# equ.net
KiCad netlist of a schematic drawn in EAGLE
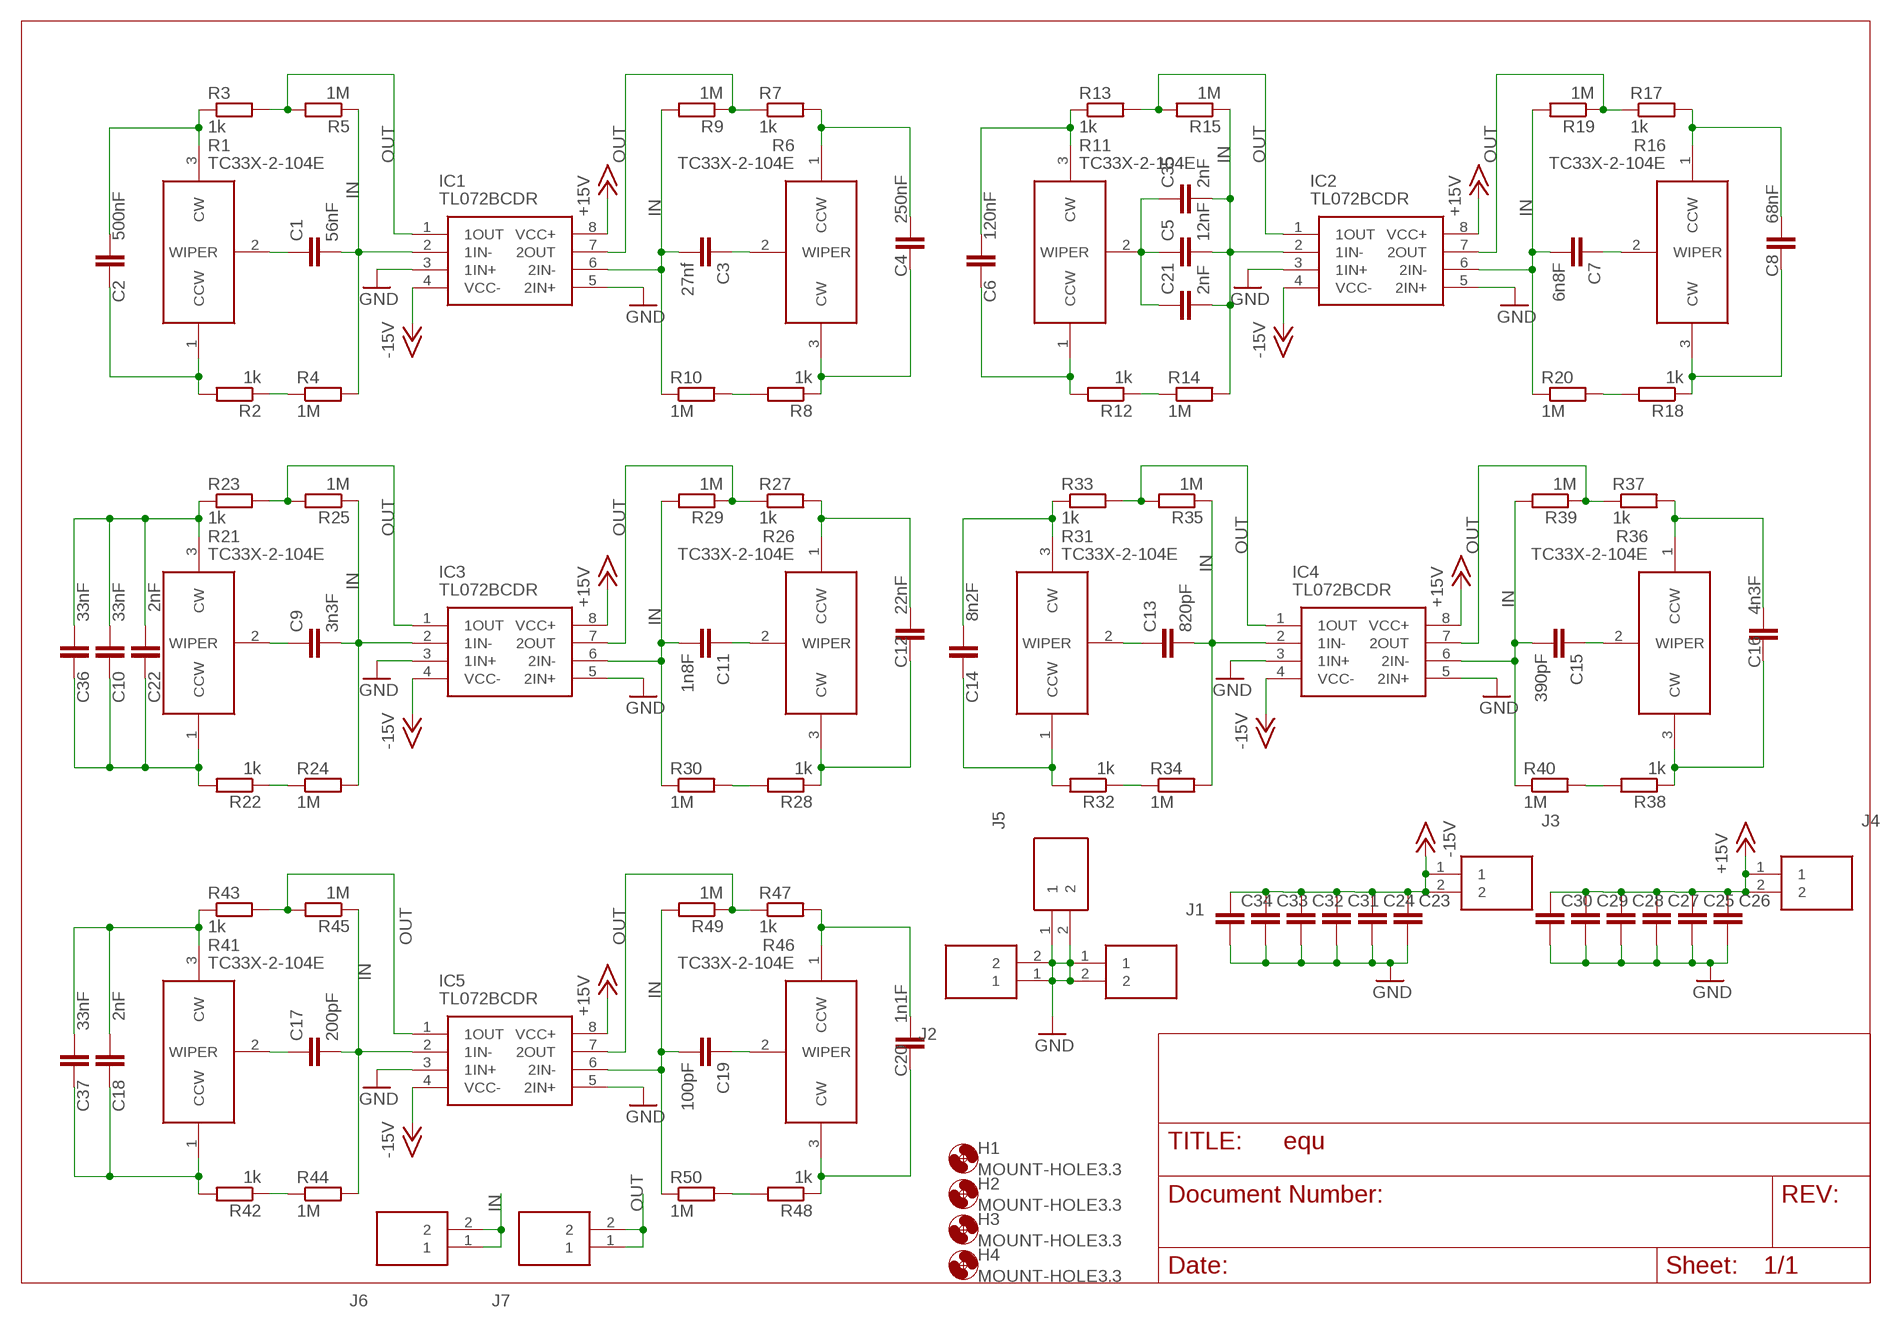
[diagram p0: schematic, sheet 1]

(export (version "E")
  (design (tool "Eeschema 10.0.6"))
  (components
    (comp (ref "C1")
      (value "56nF")
      (footprint "eagle-import:C0805")
      (libsource (lib "eagle-import") (part "rcl_334_C-EUC0805"))
    )
    (comp (ref "C2")
      (value "500nF")
      (footprint "eagle-import:C0805")
      (libsource (lib "eagle-import") (part "rcl_334_C-EUC0805"))
    )
    (comp (ref "C3")
      (value "27nf")
      (footprint "eagle-import:C0805")
      (libsource (lib "eagle-import") (part "rcl_334_C-EUC0805"))
    )
    (comp (ref "C4")
      (value "250nF")
      (footprint "eagle-import:C0805")
      (libsource (lib "eagle-import") (part "rcl_334_C-EUC0805"))
    )
    (comp (ref "C5")
      (value "12nF")
      (footprint "eagle-import:C0805")
      (libsource (lib "eagle-import") (part "rcl_334_C-EUC0805"))
    )
    (comp (ref "C6")
      (value "120nF")
      (footprint "eagle-import:C0805")
      (libsource (lib "eagle-import") (part "rcl_334_C-EUC0805"))
    )
    (comp (ref "C7")
      (value "6n8F")
      (footprint "eagle-import:C0805")
      (libsource (lib "eagle-import") (part "rcl_334_C-EUC0805"))
    )
    (comp (ref "C8")
      (value "68nF")
      (footprint "eagle-import:C0805")
      (libsource (lib "eagle-import") (part "rcl_334_C-EUC0805"))
    )
    (comp (ref "C9")
      (value "3n3F")
      (footprint "eagle-import:C0805")
      (libsource (lib "eagle-import") (part "rcl_334_C-EUC0805"))
    )
    (comp (ref "C10")
      (value "33nF")
      (footprint "eagle-import:C0805")
      (libsource (lib "eagle-import") (part "rcl_334_C-EUC0805"))
    )
    (comp (ref "C11")
      (value "1n8F")
      (footprint "eagle-import:C0805")
      (libsource (lib "eagle-import") (part "rcl_334_C-EUC0805"))
    )
    (comp (ref "C12")
      (value "22nF")
      (footprint "eagle-import:C0805")
      (libsource (lib "eagle-import") (part "rcl_334_C-EUC0805"))
    )
    (comp (ref "C13")
      (value "820pF")
      (footprint "eagle-import:C0805")
      (libsource (lib "eagle-import") (part "rcl_334_C-EUC0805"))
    )
    (comp (ref "C14")
      (value "8n2F")
      (footprint "eagle-import:C0805")
      (libsource (lib "eagle-import") (part "rcl_334_C-EUC0805"))
    )
    (comp (ref "C15")
      (value "390pF")
      (footprint "eagle-import:C0805")
      (libsource (lib "eagle-import") (part "rcl_334_C-EUC0805"))
    )
    (comp (ref "C16")
      (value "4n3F")
      (footprint "eagle-import:C0805")
      (libsource (lib "eagle-import") (part "rcl_334_C-EUC0805"))
    )
    (comp (ref "C17")
      (value "200pF")
      (footprint "eagle-import:C0805")
      (libsource (lib "eagle-import") (part "rcl_334_C-EUC0805"))
    )
    (comp (ref "C18")
      (value "2nF")
      (footprint "eagle-import:C0805")
      (libsource (lib "eagle-import") (part "rcl_334_C-EUC0805"))
    )
    (comp (ref "C19")
      (value "100pF")
      (footprint "eagle-import:C0805")
      (libsource (lib "eagle-import") (part "rcl_334_C-EUC0805"))
    )
    (comp (ref "C20")
      (value "1n1F")
      (footprint "eagle-import:C0805")
      (libsource (lib "eagle-import") (part "rcl_334_C-EUC0805"))
    )
    (comp (ref "C21")
      (value "2nF")
      (footprint "eagle-import:C0805")
      (libsource (lib "eagle-import") (part "C-EUC0805"))
    )
    (comp (ref "C22")
      (value "2nF")
      (footprint "eagle-import:C0805")
      (libsource (lib "eagle-import") (part "C-EUC0805"))
    )
    (comp (ref "C23")
      (value "C-EUC0805")
      (footprint "eagle-import:C0805")
      (libsource (lib "eagle-import") (part "C-EUC0805"))
    )
    (comp (ref "C24")
      (value "C-EUC0805")
      (footprint "eagle-import:C0805")
      (libsource (lib "eagle-import") (part "C-EUC0805"))
    )
    (comp (ref "C25")
      (value "C-EUC0805")
      (footprint "eagle-import:C0805")
      (libsource (lib "eagle-import") (part "C-EUC0805"))
    )
    (comp (ref "C26")
      (value "C-EUC0805")
      (footprint "eagle-import:C0805")
      (libsource (lib "eagle-import") (part "C-EUC0805"))
    )
    (comp (ref "C27")
      (value "C-EUC0805")
      (footprint "eagle-import:C0805")
      (libsource (lib "eagle-import") (part "C-EUC0805"))
    )
    (comp (ref "C28")
      (value "C-EUC0805")
      (footprint "eagle-import:C0805")
      (libsource (lib "eagle-import") (part "C-EUC0805"))
    )
    (comp (ref "C29")
      (value "C-EUC0805")
      (footprint "eagle-import:C0805")
      (libsource (lib "eagle-import") (part "C-EUC0805"))
    )
    (comp (ref "C30")
      (value "C-EUC0805")
      (footprint "eagle-import:C0805")
      (libsource (lib "eagle-import") (part "C-EUC0805"))
    )
    (comp (ref "C31")
      (value "C-EUC0805")
      (footprint "eagle-import:C0805")
      (libsource (lib "eagle-import") (part "C-EUC0805"))
    )
    (comp (ref "C32")
      (value "C-EUC0805")
      (footprint "eagle-import:C0805")
      (libsource (lib "eagle-import") (part "C-EUC0805"))
    )
    (comp (ref "C33")
      (value "C-EUC0805")
      (footprint "eagle-import:C0805")
      (libsource (lib "eagle-import") (part "C-EUC0805"))
    )
    (comp (ref "C34")
      (value "C-EUC0805")
      (footprint "eagle-import:C0805")
      (libsource (lib "eagle-import") (part "C-EUC0805"))
    )
    (comp (ref "C35")
      (value "2nF")
      (footprint "eagle-import:C0805")
      (libsource (lib "eagle-import") (part "C-EUC0805"))
    )
    (comp (ref "C36")
      (value "33nF")
      (footprint "eagle-import:C0805")
      (libsource (lib "eagle-import") (part "rcl_334_C-EUC0805"))
    )
    (comp (ref "C37")
      (value "33nF")
      (footprint "eagle-import:C0805")
      (libsource (lib "eagle-import") (part "rcl_334_C-EUC0805"))
    )
    (comp (ref "H1")
      (value "MOUNT-HOLE3.3")
      (footprint "eagle-import:3,3")
      (libsource (lib "eagle-import") (part "MOUNT-HOLE3.3"))
    )
    (comp (ref "H2")
      (value "MOUNT-HOLE3.3")
      (footprint "eagle-import:3,3")
      (libsource (lib "eagle-import") (part "MOUNT-HOLE3.3"))
    )
    (comp (ref "H3")
      (value "MOUNT-HOLE3.3")
      (footprint "eagle-import:3,3")
      (libsource (lib "eagle-import") (part "MOUNT-HOLE3.3"))
    )
    (comp (ref "H4")
      (value "MOUNT-HOLE3.3")
      (footprint "eagle-import:3,3")
      (libsource (lib "eagle-import") (part "MOUNT-HOLE3.3"))
    )
    (comp (ref "IC1")
      (value "TL072BCDR")
      (footprint "eagle-import:SOIC127P600X175-8N")
      (fields (field (name "MOUSER_PART_NUMBER") "595-TL072BCDR"))
      (libsource (lib "eagle-import") (part "TL072BCDR"))
    )
    (comp (ref "IC2")
      (value "TL072BCDR")
      (footprint "eagle-import:SOIC127P600X175-8N")
      (fields (field (name "MOUSER_PART_NUMBER") "595-TL072BCDR"))
      (libsource (lib "eagle-import") (part "TL072BCDR"))
    )
    (comp (ref "IC3")
      (value "TL072BCDR")
      (footprint "eagle-import:SOIC127P600X175-8N")
      (fields (field (name "MOUSER_PART_NUMBER") "595-TL072BCDR"))
      (libsource (lib "eagle-import") (part "TL072BCDR"))
    )
    (comp (ref "IC4")
      (value "TL072BCDR")
      (footprint "eagle-import:SOIC127P600X175-8N")
      (fields (field (name "MOUSER_PART_NUMBER") "595-TL072BCDR"))
      (libsource (lib "eagle-import") (part "TL072BCDR"))
    )
    (comp (ref "IC5")
      (value "TL072BCDR")
      (footprint "eagle-import:SOIC127P600X175-8N")
      (fields (field (name "MOUSER_PART_NUMBER") "595-TL072BCDR"))
      (libsource (lib "eagle-import") (part "TL072BCDR"))
    )
    (comp (ref "J1")
      (value "69190-402HLF")
      (footprint "eagle-import:HDRV2W90P0X254_1X2_508X241X858")
      (fields (field (name "RS_PART_NUMBER") "8632731"))
      (libsource (lib "eagle-import") (part "69190-402HLF"))
    )
    (comp (ref "J2")
      (value "69190-402HLF")
      (footprint "eagle-import:HDRV2W90P0X254_1X2_508X241X858")
      (fields (field (name "RS_PART_NUMBER") "8632731"))
      (libsource (lib "eagle-import") (part "69190-402HLF"))
    )
    (comp (ref "J3")
      (value "69190-402HLF")
      (footprint "eagle-import:HDRV2W90P0X254_1X2_508X241X858")
      (fields (field (name "RS_PART_NUMBER") "8632731"))
      (libsource (lib "eagle-import") (part "69190-402HLF"))
    )
    (comp (ref "J4")
      (value "69190-402HLF")
      (footprint "eagle-import:HDRV2W90P0X254_1X2_508X241X858")
      (fields (field (name "RS_PART_NUMBER") "8632731"))
      (libsource (lib "eagle-import") (part "69190-402HLF"))
    )
    (comp (ref "J5")
      (value "69190-402HLF")
      (footprint "eagle-import:HDRV2W90P0X254_1X2_508X241X858")
      (fields (field (name "RS_PART_NUMBER") "8632731"))
      (libsource (lib "eagle-import") (part "69190-402HLF"))
    )
    (comp (ref "J6")
      (value "69190-402HLF")
      (footprint "eagle-import:HDRV2W90P0X254_1X2_508X241X858")
      (fields (field (name "RS_PART_NUMBER") "8632731"))
      (libsource (lib "eagle-import") (part "69190-402HLF"))
    )
    (comp (ref "J7")
      (value "69190-402HLF")
      (footprint "eagle-import:HDRV2W90P0X254_1X2_508X241X858")
      (fields (field (name "RS_PART_NUMBER") "8632731"))
      (libsource (lib "eagle-import") (part "69190-402HLF"))
    )
    (comp (ref "R1")
      (value "TC33X-2-104E")
      (footprint "eagle-import:TC33X-2")
      (fields (field (name "MOUSER2_PART_NUMBER") "652-TC33X-2-104E"))
      (libsource (lib "eagle-import") (part "TC33X-2-104E"))
    )
    (comp (ref "R2")
      (value "1k")
      (footprint "eagle-import:R0805")
      (libsource (lib "eagle-import") (part "R-EU_R0805"))
    )
    (comp (ref "R3")
      (value "1k")
      (footprint "eagle-import:R0805")
      (libsource (lib "eagle-import") (part "R-EU_R0805"))
    )
    (comp (ref "R4")
      (value "1M")
      (footprint "eagle-import:R0805")
      (libsource (lib "eagle-import") (part "R-EU_R0805"))
    )
    (comp (ref "R5")
      (value "1M")
      (footprint "eagle-import:R0805")
      (libsource (lib "eagle-import") (part "R-EU_R0805"))
    )
    (comp (ref "R6")
      (value "TC33X-2-104E")
      (footprint "eagle-import:TC33X-2")
      (fields (field (name "MOUSER2_PART_NUMBER") "652-TC33X-2-104E"))
      (libsource (lib "eagle-import") (part "TC33X-2-104E"))
    )
    (comp (ref "R7")
      (value "1k")
      (footprint "eagle-import:R0805")
      (libsource (lib "eagle-import") (part "R-EU_R0805"))
    )
    (comp (ref "R8")
      (value "1k")
      (footprint "eagle-import:R0805")
      (libsource (lib "eagle-import") (part "R-EU_R0805"))
    )
    (comp (ref "R9")
      (value "1M")
      (footprint "eagle-import:R0805")
      (libsource (lib "eagle-import") (part "R-EU_R0805"))
    )
    (comp (ref "R10")
      (value "1M")
      (footprint "eagle-import:R0805")
      (libsource (lib "eagle-import") (part "R-EU_R0805"))
    )
    (comp (ref "R11")
      (value "TC33X-2-104E")
      (footprint "eagle-import:TC33X-2")
      (fields (field (name "MOUSER2_PART_NUMBER") "652-TC33X-2-104E"))
      (libsource (lib "eagle-import") (part "TC33X-2-104E"))
    )
    (comp (ref "R12")
      (value "1k")
      (footprint "eagle-import:R0805")
      (libsource (lib "eagle-import") (part "R-EU_R0805"))
    )
    (comp (ref "R13")
      (value "1k")
      (footprint "eagle-import:R0805")
      (libsource (lib "eagle-import") (part "R-EU_R0805"))
    )
    (comp (ref "R14")
      (value "1M")
      (footprint "eagle-import:R0805")
      (libsource (lib "eagle-import") (part "R-EU_R0805"))
    )
    (comp (ref "R15")
      (value "1M")
      (footprint "eagle-import:R0805")
      (libsource (lib "eagle-import") (part "R-EU_R0805"))
    )
    (comp (ref "R16")
      (value "TC33X-2-104E")
      (footprint "eagle-import:TC33X-2")
      (fields (field (name "MOUSER2_PART_NUMBER") "652-TC33X-2-104E"))
      (libsource (lib "eagle-import") (part "TC33X-2-104E"))
    )
    (comp (ref "R17")
      (value "1k")
      (footprint "eagle-import:R0805")
      (libsource (lib "eagle-import") (part "R-EU_R0805"))
    )
    (comp (ref "R18")
      (value "1k")
      (footprint "eagle-import:R0805")
      (libsource (lib "eagle-import") (part "R-EU_R0805"))
    )
    (comp (ref "R19")
      (value "1M")
      (footprint "eagle-import:R0805")
      (libsource (lib "eagle-import") (part "R-EU_R0805"))
    )
    (comp (ref "R20")
      (value "1M")
      (footprint "eagle-import:R0805")
      (libsource (lib "eagle-import") (part "R-EU_R0805"))
    )
    (comp (ref "R21")
      (value "TC33X-2-104E")
      (footprint "eagle-import:TC33X-2")
      (fields (field (name "MOUSER2_PART_NUMBER") "652-TC33X-2-104E"))
      (libsource (lib "eagle-import") (part "TC33X-2-104E"))
    )
    (comp (ref "R22")
      (value "1k")
      (footprint "eagle-import:R0805")
      (libsource (lib "eagle-import") (part "R-EU_R0805"))
    )
    (comp (ref "R23")
      (value "1k")
      (footprint "eagle-import:R0805")
      (libsource (lib "eagle-import") (part "R-EU_R0805"))
    )
    (comp (ref "R24")
      (value "1M")
      (footprint "eagle-import:R0805")
      (libsource (lib "eagle-import") (part "R-EU_R0805"))
    )
    (comp (ref "R25")
      (value "1M")
      (footprint "eagle-import:R0805")
      (libsource (lib "eagle-import") (part "R-EU_R0805"))
    )
    (comp (ref "R26")
      (value "TC33X-2-104E")
      (footprint "eagle-import:TC33X-2")
      (fields (field (name "MOUSER2_PART_NUMBER") "652-TC33X-2-104E"))
      (libsource (lib "eagle-import") (part "TC33X-2-104E"))
    )
    (comp (ref "R27")
      (value "1k")
      (footprint "eagle-import:R0805")
      (libsource (lib "eagle-import") (part "R-EU_R0805"))
    )
    (comp (ref "R28")
      (value "1k")
      (footprint "eagle-import:R0805")
      (libsource (lib "eagle-import") (part "R-EU_R0805"))
    )
    (comp (ref "R29")
      (value "1M")
      (footprint "eagle-import:R0805")
      (libsource (lib "eagle-import") (part "R-EU_R0805"))
    )
    (comp (ref "R30")
      (value "1M")
      (footprint "eagle-import:R0805")
      (libsource (lib "eagle-import") (part "R-EU_R0805"))
    )
    (comp (ref "R31")
      (value "TC33X-2-104E")
      (footprint "eagle-import:TC33X-2")
      (fields (field (name "MOUSER2_PART_NUMBER") "652-TC33X-2-104E"))
      (libsource (lib "eagle-import") (part "TC33X-2-104E"))
    )
    (comp (ref "R32")
      (value "1k")
      (footprint "eagle-import:R0805")
      (libsource (lib "eagle-import") (part "R-EU_R0805"))
    )
    (comp (ref "R33")
      (value "1k")
      (footprint "eagle-import:R0805")
      (libsource (lib "eagle-import") (part "R-EU_R0805"))
    )
    (comp (ref "R34")
      (value "1M")
      (footprint "eagle-import:R0805")
      (libsource (lib "eagle-import") (part "R-EU_R0805"))
    )
    (comp (ref "R35")
      (value "1M")
      (footprint "eagle-import:R0805")
      (libsource (lib "eagle-import") (part "R-EU_R0805"))
    )
    (comp (ref "R36")
      (value "TC33X-2-104E")
      (footprint "eagle-import:TC33X-2")
      (fields (field (name "MOUSER2_PART_NUMBER") "652-TC33X-2-104E"))
      (libsource (lib "eagle-import") (part "TC33X-2-104E"))
    )
    (comp (ref "R37")
      (value "1k")
      (footprint "eagle-import:R0805")
      (libsource (lib "eagle-import") (part "R-EU_R0805"))
    )
    (comp (ref "R38")
      (value "1k")
      (footprint "eagle-import:R0805")
      (libsource (lib "eagle-import") (part "R-EU_R0805"))
    )
    (comp (ref "R39")
      (value "1M")
      (footprint "eagle-import:R0805")
      (libsource (lib "eagle-import") (part "R-EU_R0805"))
    )
    (comp (ref "R40")
      (value "1M")
      (footprint "eagle-import:R0805")
      (libsource (lib "eagle-import") (part "R-EU_R0805"))
    )
    (comp (ref "R41")
      (value "TC33X-2-104E")
      (footprint "eagle-import:TC33X-2")
      (fields (field (name "MOUSER2_PART_NUMBER") "652-TC33X-2-104E"))
      (libsource (lib "eagle-import") (part "TC33X-2-104E"))
    )
    (comp (ref "R42")
      (value "1k")
      (footprint "eagle-import:R0805")
      (libsource (lib "eagle-import") (part "R-EU_R0805"))
    )
    (comp (ref "R43")
      (value "1k")
      (footprint "eagle-import:R0805")
      (libsource (lib "eagle-import") (part "R-EU_R0805"))
    )
    (comp (ref "R44")
      (value "1M")
      (footprint "eagle-import:R0805")
      (libsource (lib "eagle-import") (part "R-EU_R0805"))
    )
    (comp (ref "R45")
      (value "1M")
      (footprint "eagle-import:R0805")
      (libsource (lib "eagle-import") (part "R-EU_R0805"))
    )
    (comp (ref "R46")
      (value "TC33X-2-104E")
      (footprint "eagle-import:TC33X-2")
      (fields (field (name "MOUSER2_PART_NUMBER") "652-TC33X-2-104E"))
      (libsource (lib "eagle-import") (part "TC33X-2-104E"))
    )
    (comp (ref "R47")
      (value "1k")
      (footprint "eagle-import:R0805")
      (libsource (lib "eagle-import") (part "R-EU_R0805"))
    )
    (comp (ref "R48")
      (value "1k")
      (footprint "eagle-import:R0805")
      (libsource (lib "eagle-import") (part "R-EU_R0805"))
    )
    (comp (ref "R49")
      (value "1M")
      (footprint "eagle-import:R0805")
      (libsource (lib "eagle-import") (part "R-EU_R0805"))
    )
    (comp (ref "R50")
      (value "1M")
      (footprint "eagle-import:R0805")
      (libsource (lib "eagle-import") (part "R-EU_R0805"))
    )
  )
  (nets
    (net (code "1") (name "+15V") (class "Default")
      (node (ref "C25") (pin "1") (pinfunction "1_1") (pintype "passive"))
      (node (ref "C26") (pin "1") (pinfunction "1_1") (pintype "passive"))
      (node (ref "C27") (pin "1") (pinfunction "1_1") (pintype "passive"))
      (node (ref "C28") (pin "1") (pinfunction "1_1") (pintype "passive"))
      (node (ref "C29") (pin "1") (pinfunction "1_1") (pintype "passive"))
      (node (ref "C30") (pin "1") (pinfunction "1_1") (pintype "passive"))
      (node (ref "IC1") (pin "8") (pinfunction "VCC+_8") (pintype "bidirectional"))
      (node (ref "IC2") (pin "8") (pinfunction "VCC+_8") (pintype "bidirectional"))
      (node (ref "IC3") (pin "8") (pinfunction "VCC+_8") (pintype "bidirectional"))
      (node (ref "IC4") (pin "8") (pinfunction "VCC+_8") (pintype "bidirectional"))
      (node (ref "IC5") (pin "8") (pinfunction "VCC+_8") (pintype "bidirectional"))
      (node (ref "J4") (pin "1") (pinfunction "1_1") (pintype "bidirectional"))
      (node (ref "J4") (pin "2") (pinfunction "2_2") (pintype "bidirectional"))
    )
    (net (code "2") (name "-15V") (class "Default")
      (node (ref "C23") (pin "1") (pinfunction "1_1") (pintype "passive"))
      (node (ref "C24") (pin "1") (pinfunction "1_1") (pintype "passive"))
      (node (ref "C31") (pin "1") (pinfunction "1_1") (pintype "passive"))
      (node (ref "C32") (pin "1") (pinfunction "1_1") (pintype "passive"))
      (node (ref "C33") (pin "1") (pinfunction "1_1") (pintype "passive"))
      (node (ref "C34") (pin "1") (pinfunction "1_1") (pintype "passive"))
      (node (ref "IC1") (pin "4") (pinfunction "VCC-_4") (pintype "bidirectional"))
      (node (ref "IC2") (pin "4") (pinfunction "VCC-_4") (pintype "bidirectional"))
      (node (ref "IC3") (pin "4") (pinfunction "VCC-_4") (pintype "bidirectional"))
      (node (ref "IC4") (pin "4") (pinfunction "VCC-_4") (pintype "bidirectional"))
      (node (ref "IC5") (pin "4") (pinfunction "VCC-_4") (pintype "bidirectional"))
      (node (ref "J3") (pin "1") (pinfunction "1_1") (pintype "bidirectional"))
      (node (ref "J3") (pin "2") (pinfunction "2_2") (pintype "bidirectional"))
    )
    (net (code "3") (name "/IN") (class "Default")
      (node (ref "C1") (pin "2") (pinfunction "2_2") (pintype "passive"))
      (node (ref "C11") (pin "2") (pinfunction "2_2") (pintype "passive"))
      (node (ref "C13") (pin "2") (pinfunction "2_2") (pintype "passive"))
      (node (ref "C15") (pin "2") (pinfunction "2_2") (pintype "passive"))
      (node (ref "C17") (pin "2") (pinfunction "2_2") (pintype "passive"))
      (node (ref "C19") (pin "2") (pinfunction "2_2") (pintype "passive"))
      (node (ref "C21") (pin "2") (pinfunction "2_2") (pintype "passive"))
      (node (ref "C3") (pin "2") (pinfunction "2_2") (pintype "passive"))
      (node (ref "C35") (pin "2") (pinfunction "2_2") (pintype "passive"))
      (node (ref "C5") (pin "2") (pinfunction "2_2") (pintype "passive"))
      (node (ref "C7") (pin "2") (pinfunction "2_2") (pintype "passive"))
      (node (ref "C9") (pin "2") (pinfunction "2_2") (pintype "passive"))
      (node (ref "IC1") (pin "2") (pinfunction "1IN-_2") (pintype "bidirectional"))
      (node (ref "IC1") (pin "6") (pinfunction "2IN-_6") (pintype "bidirectional"))
      (node (ref "IC2") (pin "2") (pinfunction "1IN-_2") (pintype "bidirectional"))
      (node (ref "IC2") (pin "6") (pinfunction "2IN-_6") (pintype "bidirectional"))
      (node (ref "IC3") (pin "2") (pinfunction "1IN-_2") (pintype "bidirectional"))
      (node (ref "IC3") (pin "6") (pinfunction "2IN-_6") (pintype "bidirectional"))
      (node (ref "IC4") (pin "2") (pinfunction "1IN-_2") (pintype "bidirectional"))
      (node (ref "IC4") (pin "6") (pinfunction "2IN-_6") (pintype "bidirectional"))
      (node (ref "IC5") (pin "2") (pinfunction "1IN-_2") (pintype "bidirectional"))
      (node (ref "IC5") (pin "6") (pinfunction "2IN-_6") (pintype "bidirectional"))
      (node (ref "J6") (pin "1") (pinfunction "1_1") (pintype "bidirectional"))
      (node (ref "J6") (pin "2") (pinfunction "2_2") (pintype "bidirectional"))
      (node (ref "R10") (pin "1") (pinfunction "1_1") (pintype "passive"))
      (node (ref "R14") (pin "2") (pinfunction "2_2") (pintype "passive"))
      (node (ref "R15") (pin "1") (pinfunction "1_1") (pintype "passive"))
      (node (ref "R19") (pin "2") (pinfunction "2_2") (pintype "passive"))
      (node (ref "R20") (pin "1") (pinfunction "1_1") (pintype "passive"))
      (node (ref "R24") (pin "2") (pinfunction "2_2") (pintype "passive"))
      (node (ref "R25") (pin "1") (pinfunction "1_1") (pintype "passive"))
      (node (ref "R29") (pin "2") (pinfunction "2_2") (pintype "passive"))
      (node (ref "R30") (pin "1") (pinfunction "1_1") (pintype "passive"))
      (node (ref "R34") (pin "2") (pinfunction "2_2") (pintype "passive"))
      (node (ref "R35") (pin "1") (pinfunction "1_1") (pintype "passive"))
      (node (ref "R39") (pin "2") (pinfunction "2_2") (pintype "passive"))
      (node (ref "R4") (pin "2") (pinfunction "2_2") (pintype "passive"))
      (node (ref "R40") (pin "1") (pinfunction "1_1") (pintype "passive"))
      (node (ref "R44") (pin "2") (pinfunction "2_2") (pintype "passive"))
      (node (ref "R45") (pin "1") (pinfunction "1_1") (pintype "passive"))
      (node (ref "R49") (pin "2") (pinfunction "2_2") (pintype "passive"))
      (node (ref "R5") (pin "1") (pinfunction "1_1") (pintype "passive"))
      (node (ref "R50") (pin "1") (pinfunction "1_1") (pintype "passive"))
      (node (ref "R9") (pin "2") (pinfunction "2_2") (pintype "passive"))
    )
    (net (code "4") (name "/OUT") (class "Default")
      (node (ref "IC1") (pin "1") (pinfunction "1OUT_1") (pintype "bidirectional"))
      (node (ref "IC1") (pin "7") (pinfunction "2OUT_7") (pintype "bidirectional"))
      (node (ref "IC2") (pin "1") (pinfunction "1OUT_1") (pintype "bidirectional"))
      (node (ref "IC2") (pin "7") (pinfunction "2OUT_7") (pintype "bidirectional"))
      (node (ref "IC3") (pin "1") (pinfunction "1OUT_1") (pintype "bidirectional"))
      (node (ref "IC3") (pin "7") (pinfunction "2OUT_7") (pintype "bidirectional"))
      (node (ref "IC4") (pin "1") (pinfunction "1OUT_1") (pintype "bidirectional"))
      (node (ref "IC4") (pin "7") (pinfunction "2OUT_7") (pintype "bidirectional"))
      (node (ref "IC5") (pin "1") (pinfunction "1OUT_1") (pintype "bidirectional"))
      (node (ref "IC5") (pin "7") (pinfunction "2OUT_7") (pintype "bidirectional"))
      (node (ref "J7") (pin "1") (pinfunction "1_1") (pintype "bidirectional"))
      (node (ref "J7") (pin "2") (pinfunction "2_2") (pintype "bidirectional"))
      (node (ref "R13") (pin "2") (pinfunction "2_2") (pintype "passive"))
      (node (ref "R15") (pin "2") (pinfunction "2_2") (pintype "passive"))
      (node (ref "R17") (pin "1") (pinfunction "1_1") (pintype "passive"))
      (node (ref "R19") (pin "1") (pinfunction "1_1") (pintype "passive"))
      (node (ref "R23") (pin "2") (pinfunction "2_2") (pintype "passive"))
      (node (ref "R25") (pin "2") (pinfunction "2_2") (pintype "passive"))
      (node (ref "R27") (pin "1") (pinfunction "1_1") (pintype "passive"))
      (node (ref "R29") (pin "1") (pinfunction "1_1") (pintype "passive"))
      (node (ref "R3") (pin "2") (pinfunction "2_2") (pintype "passive"))
      (node (ref "R33") (pin "2") (pinfunction "2_2") (pintype "passive"))
      (node (ref "R35") (pin "2") (pinfunction "2_2") (pintype "passive"))
      (node (ref "R37") (pin "1") (pinfunction "1_1") (pintype "passive"))
      (node (ref "R39") (pin "1") (pinfunction "1_1") (pintype "passive"))
      (node (ref "R43") (pin "2") (pinfunction "2_2") (pintype "passive"))
      (node (ref "R45") (pin "2") (pinfunction "2_2") (pintype "passive"))
      (node (ref "R47") (pin "1") (pinfunction "1_1") (pintype "passive"))
      (node (ref "R49") (pin "1") (pinfunction "1_1") (pintype "passive"))
      (node (ref "R5") (pin "2") (pinfunction "2_2") (pintype "passive"))
      (node (ref "R7") (pin "1") (pinfunction "1_1") (pintype "passive"))
      (node (ref "R9") (pin "1") (pinfunction "1_1") (pintype "passive"))
    )
    (net (code "5") (name "GND") (class "Default")
      (node (ref "C23") (pin "2") (pinfunction "2_2") (pintype "passive"))
      (node (ref "C24") (pin "2") (pinfunction "2_2") (pintype "passive"))
      (node (ref "C25") (pin "2") (pinfunction "2_2") (pintype "passive"))
      (node (ref "C26") (pin "2") (pinfunction "2_2") (pintype "passive"))
      (node (ref "C27") (pin "2") (pinfunction "2_2") (pintype "passive"))
      (node (ref "C28") (pin "2") (pinfunction "2_2") (pintype "passive"))
      (node (ref "C29") (pin "2") (pinfunction "2_2") (pintype "passive"))
      (node (ref "C30") (pin "2") (pinfunction "2_2") (pintype "passive"))
      (node (ref "C31") (pin "2") (pinfunction "2_2") (pintype "passive"))
      (node (ref "C32") (pin "2") (pinfunction "2_2") (pintype "passive"))
      (node (ref "C33") (pin "2") (pinfunction "2_2") (pintype "passive"))
      (node (ref "C34") (pin "2") (pinfunction "2_2") (pintype "passive"))
      (node (ref "IC1") (pin "3") (pinfunction "1IN+_3") (pintype "bidirectional"))
      (node (ref "IC1") (pin "5") (pinfunction "2IN+_5") (pintype "bidirectional"))
      (node (ref "IC2") (pin "3") (pinfunction "1IN+_3") (pintype "bidirectional"))
      (node (ref "IC2") (pin "5") (pinfunction "2IN+_5") (pintype "bidirectional"))
      (node (ref "IC3") (pin "3") (pinfunction "1IN+_3") (pintype "bidirectional"))
      (node (ref "IC3") (pin "5") (pinfunction "2IN+_5") (pintype "bidirectional"))
      (node (ref "IC4") (pin "3") (pinfunction "1IN+_3") (pintype "bidirectional"))
      (node (ref "IC4") (pin "5") (pinfunction "2IN+_5") (pintype "bidirectional"))
      (node (ref "IC5") (pin "3") (pinfunction "1IN+_3") (pintype "bidirectional"))
      (node (ref "IC5") (pin "5") (pinfunction "2IN+_5") (pintype "bidirectional"))
      (node (ref "J1") (pin "1") (pinfunction "1_1") (pintype "bidirectional"))
      (node (ref "J1") (pin "2") (pinfunction "2_2") (pintype "bidirectional"))
      (node (ref "J2") (pin "1") (pinfunction "1_1") (pintype "bidirectional"))
      (node (ref "J2") (pin "2") (pinfunction "2_2") (pintype "bidirectional"))
      (node (ref "J5") (pin "1") (pinfunction "1_1") (pintype "bidirectional"))
      (node (ref "J5") (pin "2") (pinfunction "2_2") (pintype "bidirectional"))
    )
    (net (code "6") (name "Net-(R1-CCW)") (class "Default")
      (node (ref "C2") (pin "1") (pinfunction "1_1") (pintype "passive"))
      (node (ref "R1") (pin "1") (pinfunction "CCW_1") (pintype "bidirectional"))
      (node (ref "R2") (pin "2") (pinfunction "2_2") (pintype "passive"))
    )
    (net (code "7") (name "Net-(R1-CW)") (class "Default")
      (node (ref "C2") (pin "2") (pinfunction "2_2") (pintype "passive"))
      (node (ref "R1") (pin "3") (pinfunction "CW_3") (pintype "bidirectional"))
      (node (ref "R3") (pin "1") (pinfunction "1_1") (pintype "passive"))
    )
    (net (code "8") (name "Net-(R1-WIPER)") (class "Default")
      (node (ref "C1") (pin "1") (pinfunction "1_1") (pintype "passive"))
      (node (ref "R1") (pin "2") (pinfunction "WIPER_2") (pintype "bidirectional"))
    )
    (net (code "9") (name "Net-(R2-Pad1)") (class "Default")
      (node (ref "R2") (pin "1") (pinfunction "1_1") (pintype "passive"))
      (node (ref "R4") (pin "1") (pinfunction "1_1") (pintype "passive"))
    )
    (net (code "10") (name "Net-(R6-CCW)") (class "Default")
      (node (ref "C4") (pin "1") (pinfunction "1_1") (pintype "passive"))
      (node (ref "R6") (pin "1") (pinfunction "CCW_1") (pintype "bidirectional"))
      (node (ref "R7") (pin "2") (pinfunction "2_2") (pintype "passive"))
    )
    (net (code "11") (name "Net-(R6-CW)") (class "Default")
      (node (ref "C4") (pin "2") (pinfunction "2_2") (pintype "passive"))
      (node (ref "R6") (pin "3") (pinfunction "CW_3") (pintype "bidirectional"))
      (node (ref "R8") (pin "1") (pinfunction "1_1") (pintype "passive"))
    )
    (net (code "12") (name "Net-(R6-WIPER)") (class "Default")
      (node (ref "C3") (pin "1") (pinfunction "1_1") (pintype "passive"))
      (node (ref "R6") (pin "2") (pinfunction "WIPER_2") (pintype "bidirectional"))
    )
    (net (code "13") (name "Net-(R10-Pad2)") (class "Default")
      (node (ref "R10") (pin "2") (pinfunction "2_2") (pintype "passive"))
      (node (ref "R8") (pin "2") (pinfunction "2_2") (pintype "passive"))
    )
    (net (code "14") (name "Net-(R11-CCW)") (class "Default")
      (node (ref "C6") (pin "1") (pinfunction "1_1") (pintype "passive"))
      (node (ref "R11") (pin "1") (pinfunction "CCW_1") (pintype "bidirectional"))
      (node (ref "R12") (pin "2") (pinfunction "2_2") (pintype "passive"))
    )
    (net (code "15") (name "Net-(R11-CW)") (class "Default")
      (node (ref "C6") (pin "2") (pinfunction "2_2") (pintype "passive"))
      (node (ref "R11") (pin "3") (pinfunction "CW_3") (pintype "bidirectional"))
      (node (ref "R13") (pin "1") (pinfunction "1_1") (pintype "passive"))
    )
    (net (code "16") (name "Net-(R11-WIPER)") (class "Default")
      (node (ref "C21") (pin "1") (pinfunction "1_1") (pintype "passive"))
      (node (ref "C35") (pin "1") (pinfunction "1_1") (pintype "passive"))
      (node (ref "C5") (pin "1") (pinfunction "1_1") (pintype "passive"))
      (node (ref "R11") (pin "2") (pinfunction "WIPER_2") (pintype "bidirectional"))
    )
    (net (code "17") (name "Net-(R12-Pad1)") (class "Default")
      (node (ref "R12") (pin "1") (pinfunction "1_1") (pintype "passive"))
      (node (ref "R14") (pin "1") (pinfunction "1_1") (pintype "passive"))
    )
    (net (code "18") (name "Net-(R16-CCW)") (class "Default")
      (node (ref "C8") (pin "1") (pinfunction "1_1") (pintype "passive"))
      (node (ref "R16") (pin "1") (pinfunction "CCW_1") (pintype "bidirectional"))
      (node (ref "R17") (pin "2") (pinfunction "2_2") (pintype "passive"))
    )
    (net (code "19") (name "Net-(R16-CW)") (class "Default")
      (node (ref "C8") (pin "2") (pinfunction "2_2") (pintype "passive"))
      (node (ref "R16") (pin "3") (pinfunction "CW_3") (pintype "bidirectional"))
      (node (ref "R18") (pin "1") (pinfunction "1_1") (pintype "passive"))
    )
    (net (code "20") (name "Net-(R16-WIPER)") (class "Default")
      (node (ref "C7") (pin "1") (pinfunction "1_1") (pintype "passive"))
      (node (ref "R16") (pin "2") (pinfunction "WIPER_2") (pintype "bidirectional"))
    )
    (net (code "21") (name "Net-(R18-Pad2)") (class "Default")
      (node (ref "R18") (pin "2") (pinfunction "2_2") (pintype "passive"))
      (node (ref "R20") (pin "2") (pinfunction "2_2") (pintype "passive"))
    )
    (net (code "22") (name "Net-(R21-CCW)") (class "Default")
      (node (ref "C10") (pin "1") (pinfunction "1_1") (pintype "passive"))
      (node (ref "C22") (pin "2") (pinfunction "2_2") (pintype "passive"))
      (node (ref "C36") (pin "1") (pinfunction "1_1") (pintype "passive"))
      (node (ref "R21") (pin "1") (pinfunction "CCW_1") (pintype "bidirectional"))
      (node (ref "R22") (pin "2") (pinfunction "2_2") (pintype "passive"))
    )
    (net (code "23") (name "Net-(R21-CW)") (class "Default")
      (node (ref "C10") (pin "2") (pinfunction "2_2") (pintype "passive"))
      (node (ref "C22") (pin "1") (pinfunction "1_1") (pintype "passive"))
      (node (ref "C36") (pin "2") (pinfunction "2_2") (pintype "passive"))
      (node (ref "R21") (pin "3") (pinfunction "CW_3") (pintype "bidirectional"))
      (node (ref "R23") (pin "1") (pinfunction "1_1") (pintype "passive"))
    )
    (net (code "24") (name "Net-(R21-WIPER)") (class "Default")
      (node (ref "C9") (pin "1") (pinfunction "1_1") (pintype "passive"))
      (node (ref "R21") (pin "2") (pinfunction "WIPER_2") (pintype "bidirectional"))
    )
    (net (code "25") (name "Net-(R22-Pad1)") (class "Default")
      (node (ref "R22") (pin "1") (pinfunction "1_1") (pintype "passive"))
      (node (ref "R24") (pin "1") (pinfunction "1_1") (pintype "passive"))
    )
    (net (code "26") (name "Net-(R26-CCW)") (class "Default")
      (node (ref "C12") (pin "1") (pinfunction "1_1") (pintype "passive"))
      (node (ref "R26") (pin "1") (pinfunction "CCW_1") (pintype "bidirectional"))
      (node (ref "R27") (pin "2") (pinfunction "2_2") (pintype "passive"))
    )
    (net (code "27") (name "Net-(R26-CW)") (class "Default")
      (node (ref "C12") (pin "2") (pinfunction "2_2") (pintype "passive"))
      (node (ref "R26") (pin "3") (pinfunction "CW_3") (pintype "bidirectional"))
      (node (ref "R28") (pin "1") (pinfunction "1_1") (pintype "passive"))
    )
    (net (code "28") (name "Net-(R26-WIPER)") (class "Default")
      (node (ref "C11") (pin "1") (pinfunction "1_1") (pintype "passive"))
      (node (ref "R26") (pin "2") (pinfunction "WIPER_2") (pintype "bidirectional"))
    )
    (net (code "29") (name "Net-(R28-Pad2)") (class "Default")
      (node (ref "R28") (pin "2") (pinfunction "2_2") (pintype "passive"))
      (node (ref "R30") (pin "2") (pinfunction "2_2") (pintype "passive"))
    )
    (net (code "30") (name "Net-(R31-CCW)") (class "Default")
      (node (ref "C14") (pin "1") (pinfunction "1_1") (pintype "passive"))
      (node (ref "R31") (pin "1") (pinfunction "CCW_1") (pintype "bidirectional"))
      (node (ref "R32") (pin "2") (pinfunction "2_2") (pintype "passive"))
    )
    (net (code "31") (name "Net-(R31-CW)") (class "Default")
      (node (ref "C14") (pin "2") (pinfunction "2_2") (pintype "passive"))
      (node (ref "R31") (pin "3") (pinfunction "CW_3") (pintype "bidirectional"))
      (node (ref "R33") (pin "1") (pinfunction "1_1") (pintype "passive"))
    )
    (net (code "32") (name "Net-(R31-WIPER)") (class "Default")
      (node (ref "C13") (pin "1") (pinfunction "1_1") (pintype "passive"))
      (node (ref "R31") (pin "2") (pinfunction "WIPER_2") (pintype "bidirectional"))
    )
    (net (code "33") (name "Net-(R32-Pad1)") (class "Default")
      (node (ref "R32") (pin "1") (pinfunction "1_1") (pintype "passive"))
      (node (ref "R34") (pin "1") (pinfunction "1_1") (pintype "passive"))
    )
    (net (code "34") (name "Net-(R36-CCW)") (class "Default")
      (node (ref "C16") (pin "1") (pinfunction "1_1") (pintype "passive"))
      (node (ref "R36") (pin "1") (pinfunction "CCW_1") (pintype "bidirectional"))
      (node (ref "R37") (pin "2") (pinfunction "2_2") (pintype "passive"))
    )
    (net (code "35") (name "Net-(R36-CW)") (class "Default")
      (node (ref "C16") (pin "2") (pinfunction "2_2") (pintype "passive"))
      (node (ref "R36") (pin "3") (pinfunction "CW_3") (pintype "bidirectional"))
      (node (ref "R38") (pin "1") (pinfunction "1_1") (pintype "passive"))
    )
    (net (code "36") (name "Net-(R36-WIPER)") (class "Default")
      (node (ref "C15") (pin "1") (pinfunction "1_1") (pintype "passive"))
      (node (ref "R36") (pin "2") (pinfunction "WIPER_2") (pintype "bidirectional"))
    )
    (net (code "37") (name "Net-(R38-Pad2)") (class "Default")
      (node (ref "R38") (pin "2") (pinfunction "2_2") (pintype "passive"))
      (node (ref "R40") (pin "2") (pinfunction "2_2") (pintype "passive"))
    )
    (net (code "38") (name "Net-(R41-CCW)") (class "Default")
      (node (ref "C18") (pin "1") (pinfunction "1_1") (pintype "passive"))
      (node (ref "C37") (pin "1") (pinfunction "1_1") (pintype "passive"))
      (node (ref "R41") (pin "1") (pinfunction "CCW_1") (pintype "bidirectional"))
      (node (ref "R42") (pin "2") (pinfunction "2_2") (pintype "passive"))
    )
    (net (code "39") (name "Net-(R41-CW)") (class "Default")
      (node (ref "C18") (pin "2") (pinfunction "2_2") (pintype "passive"))
      (node (ref "C37") (pin "2") (pinfunction "2_2") (pintype "passive"))
      (node (ref "R41") (pin "3") (pinfunction "CW_3") (pintype "bidirectional"))
      (node (ref "R43") (pin "1") (pinfunction "1_1") (pintype "passive"))
    )
    (net (code "40") (name "Net-(R41-WIPER)") (class "Default")
      (node (ref "C17") (pin "1") (pinfunction "1_1") (pintype "passive"))
      (node (ref "R41") (pin "2") (pinfunction "WIPER_2") (pintype "bidirectional"))
    )
    (net (code "41") (name "Net-(R42-Pad1)") (class "Default")
      (node (ref "R42") (pin "1") (pinfunction "1_1") (pintype "passive"))
      (node (ref "R44") (pin "1") (pinfunction "1_1") (pintype "passive"))
    )
    (net (code "42") (name "Net-(R46-CCW)") (class "Default")
      (node (ref "C20") (pin "1") (pinfunction "1_1") (pintype "passive"))
      (node (ref "R46") (pin "1") (pinfunction "CCW_1") (pintype "bidirectional"))
      (node (ref "R47") (pin "2") (pinfunction "2_2") (pintype "passive"))
    )
    (net (code "43") (name "Net-(R46-CW)") (class "Default")
      (node (ref "C20") (pin "2") (pinfunction "2_2") (pintype "passive"))
      (node (ref "R46") (pin "3") (pinfunction "CW_3") (pintype "bidirectional"))
      (node (ref "R48") (pin "1") (pinfunction "1_1") (pintype "passive"))
    )
    (net (code "44") (name "Net-(R46-WIPER)") (class "Default")
      (node (ref "C19") (pin "1") (pinfunction "1_1") (pintype "passive"))
      (node (ref "R46") (pin "2") (pinfunction "WIPER_2") (pintype "bidirectional"))
    )
    (net (code "45") (name "Net-(R48-Pad2)") (class "Default")
      (node (ref "R48") (pin "2") (pinfunction "2_2") (pintype "passive"))
      (node (ref "R50") (pin "2") (pinfunction "2_2") (pintype "passive"))
    )
  )
)
